# BSAT_-_Battery_Shield.net
KiCad netlist of a schematic drawn in EAGLE
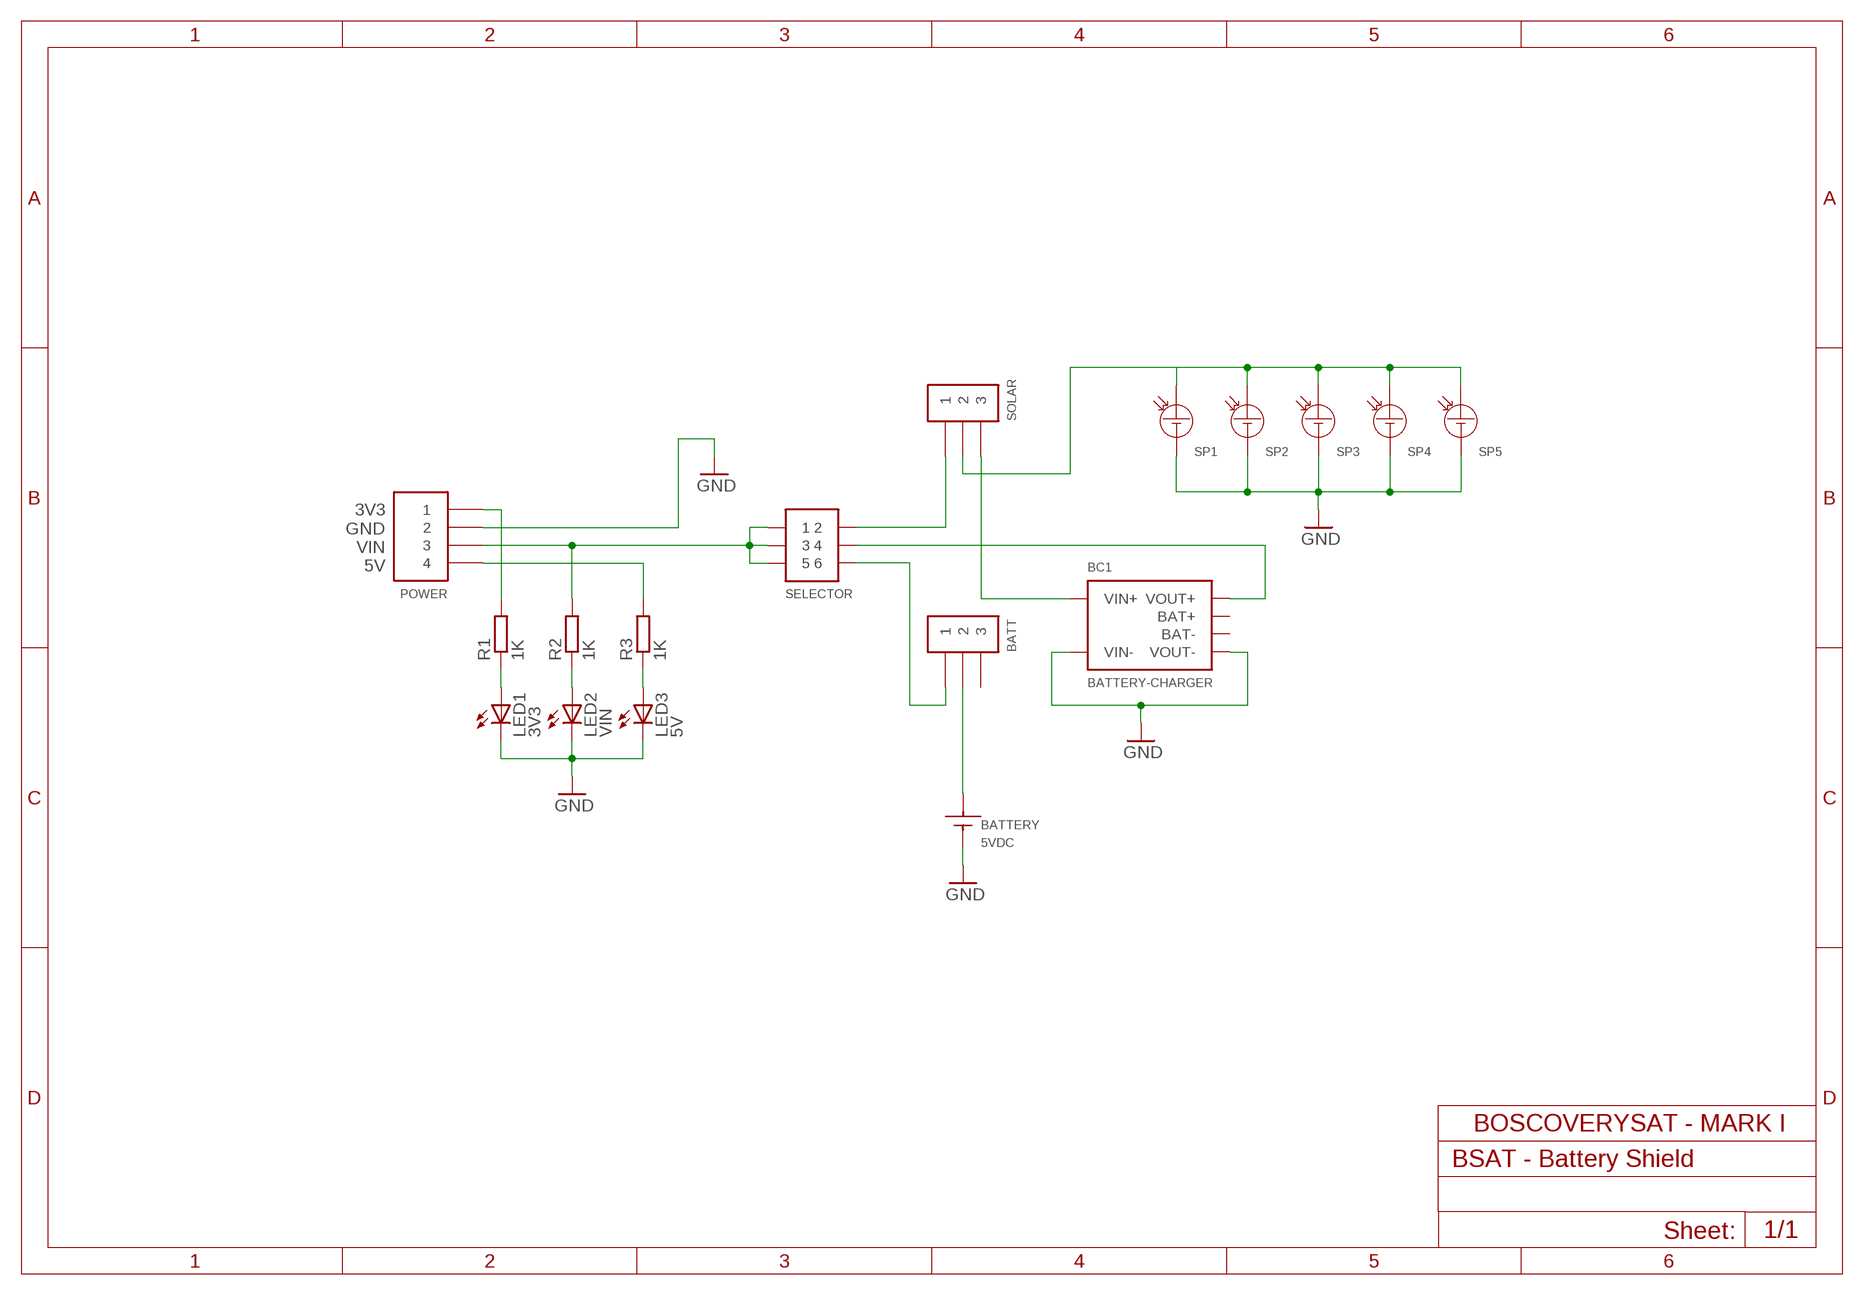
[diagram p0: schematic, sheet 1]

(export (version "E")
  (design (tool "Eeschema 10.0.6"))
  (components
    (comp (ref "5VDC")
      (value "BATTERY")
      (footprint "eagle-import:SOLAR-PANEL")
      (libsource (lib "eagle-import") (part "BATTERY"))
    )
    (comp (ref "BATT")
      (value "3-PIN-JUMPER")
      (footprint "eagle-import:3-PIN-JUMPER")
      (libsource (lib "eagle-import") (part "3-PIN-JUMPER"))
    )
    (comp (ref "BC1")
      (value "BATTERY-CHARGER")
      (footprint "eagle-import:BATTERY-CHARGER")
      (libsource (lib "eagle-import") (part "BATTERY-CHARGER"))
    )
    (comp (ref "LED1")
      (value "3V3")
      (footprint "eagle-import:LED3MM")
      (libsource (lib "eagle-import") (part "LED3MM"))
    )
    (comp (ref "LED2")
      (value "VIN")
      (footprint "eagle-import:LED3MM")
      (libsource (lib "eagle-import") (part "LED3MM"))
    )
    (comp (ref "LED3")
      (value "5V")
      (footprint "eagle-import:LED3MM")
      (libsource (lib "eagle-import") (part "LED3MM"))
    )
    (comp (ref "POWER")
      (value "4-PIN-DUAL-BUS")
      (footprint "eagle-import:4-PIN-LINEAL-JUMPER")
      (libsource (lib "eagle-import") (part "4-PIN-DUAL-BUS"))
    )
    (comp (ref "R1")
      (value "1K")
      (footprint "eagle-import:0207_12")
      (libsource (lib "eagle-import") (part "R-EU_0207/12"))
    )
    (comp (ref "R2")
      (value "1K")
      (footprint "eagle-import:0207_12")
      (libsource (lib "eagle-import") (part "R-EU_0207/12"))
    )
    (comp (ref "R3")
      (value "1K")
      (footprint "eagle-import:0207_12")
      (libsource (lib "eagle-import") (part "R-EU_0207/12"))
    )
    (comp (ref "SELECTOR")
      (value "3-PIN-PARALEL-JUMPER")
      (footprint "eagle-import:3-PIN-PARALEL-JUMPER")
      (libsource (lib "eagle-import") (part "3-PIN-PARALEL-JUMPER"))
    )
    (comp (ref "SOLAR")
      (value "3-PIN-JUMPER")
      (footprint "eagle-import:3-PIN-JUMPER")
      (libsource (lib "eagle-import") (part "3-PIN-JUMPER"))
    )
    (comp (ref "SP1")
      (value "SOLAR-PANEL2")
      (footprint "eagle-import:SOLAR-PANEL")
      (libsource (lib "eagle-import") (part "SOLAR-PANEL2"))
    )
    (comp (ref "SP2")
      (value "SOLAR-PANEL2")
      (footprint "eagle-import:SOLAR-PANEL")
      (libsource (lib "eagle-import") (part "SOLAR-PANEL2"))
    )
    (comp (ref "SP3")
      (value "SOLAR-PANEL2")
      (footprint "eagle-import:SOLAR-PANEL")
      (libsource (lib "eagle-import") (part "SOLAR-PANEL2"))
    )
    (comp (ref "SP4")
      (value "SOLAR-PANEL2")
      (footprint "eagle-import:SOLAR-PANEL")
      (libsource (lib "eagle-import") (part "SOLAR-PANEL2"))
    )
    (comp (ref "SP5")
      (value "SOLAR-PANEL2")
      (footprint "eagle-import:SOLAR-PANEL")
      (libsource (lib "eagle-import") (part "SOLAR-PANEL2"))
    )
  )
  (nets
    (net (code "1") (name "GND") (class "Default")
      (node (ref "5VDC") (pin "NEG") (pinfunction "NEG_NEG") (pintype "bidirectional"))
      (node (ref "BC1") (pin "VIN-") (pinfunction "VIN-_VIN-") (pintype "bidirectional"))
      (node (ref "BC1") (pin "VOUT-") (pinfunction "VOUT-_VOUT-") (pintype "bidirectional"))
      (node (ref "LED1") (pin "K") (pinfunction "C_K") (pintype "passive"))
      (node (ref "LED2") (pin "K") (pinfunction "C_K") (pintype "passive"))
      (node (ref "LED3") (pin "K") (pinfunction "C_K") (pintype "passive"))
      (node (ref "POWER") (pin "2A") (pinfunction "2_2A") (pintype "bidirectional"))
      (node (ref "POWER") (pin "2B") (pinfunction "2_2B") (pintype "bidirectional"))
      (node (ref "SP1") (pin "NEG") (pinfunction "P$2_NEG") (pintype "bidirectional"))
      (node (ref "SP2") (pin "NEG") (pinfunction "P$2_NEG") (pintype "bidirectional"))
      (node (ref "SP3") (pin "NEG") (pinfunction "P$2_NEG") (pintype "bidirectional"))
      (node (ref "SP4") (pin "NEG") (pinfunction "P$2_NEG") (pintype "bidirectional"))
      (node (ref "SP5") (pin "NEG") (pinfunction "P$2_NEG") (pintype "bidirectional"))
    )
    (net (code "2") (name "Net-(5VDC-PadPOS)") (class "Default")
      (node (ref "5VDC") (pin "POS") (pinfunction "POS_POS") (pintype "bidirectional"))
      (node (ref "BATT") (pin "2") (pinfunction "2_2") (pintype "bidirectional"))
    )
    (net (code "3") (name "Net-(BATT-Pad1)") (class "Default")
      (node (ref "BATT") (pin "1") (pinfunction "1_1") (pintype "bidirectional"))
      (node (ref "SELECTOR") (pin "6") (pinfunction "6_6") (pintype "bidirectional"))
    )
    (net (code "4") (name "Net-(BC1-PadVIN+)") (class "Default")
      (node (ref "BC1") (pin "VIN+") (pinfunction "VIN+_VIN+") (pintype "bidirectional"))
      (node (ref "SOLAR") (pin "3") (pinfunction "3_3") (pintype "bidirectional"))
    )
    (net (code "5") (name "Net-(BC1-PadVOUT+)") (class "Default")
      (node (ref "BC1") (pin "VOUT+") (pinfunction "VOUT+_VOUT+") (pintype "bidirectional"))
      (node (ref "SELECTOR") (pin "4") (pinfunction "4_4") (pintype "bidirectional"))
    )
    (net (code "6") (name "Net-(LED1-PadA)") (class "Default")
      (node (ref "LED1") (pin "A") (pinfunction "A_A") (pintype "passive"))
      (node (ref "R1") (pin "1") (pinfunction "1_1") (pintype "passive"))
    )
    (net (code "7") (name "Net-(LED2-PadA)") (class "Default")
      (node (ref "LED2") (pin "A") (pinfunction "A_A") (pintype "passive"))
      (node (ref "R2") (pin "1") (pinfunction "1_1") (pintype "passive"))
    )
    (net (code "8") (name "Net-(LED3-PadA)") (class "Default")
      (node (ref "LED3") (pin "A") (pinfunction "A_A") (pintype "passive"))
      (node (ref "R3") (pin "1") (pinfunction "1_1") (pintype "passive"))
    )
    (net (code "9") (name "Net-(POWER-1-Pad1A)") (class "Default")
      (node (ref "POWER") (pin "1A") (pinfunction "1_1A") (pintype "bidirectional"))
      (node (ref "POWER") (pin "1B") (pinfunction "1_1B") (pintype "bidirectional"))
      (node (ref "R1") (pin "2") (pinfunction "2_2") (pintype "passive"))
    )
    (net (code "10") (name "Net-(POWER-3-Pad3A)") (class "Default")
      (node (ref "POWER") (pin "3A") (pinfunction "3_3A") (pintype "bidirectional"))
      (node (ref "POWER") (pin "3B") (pinfunction "3_3B") (pintype "bidirectional"))
      (node (ref "R2") (pin "2") (pinfunction "2_2") (pintype "passive"))
      (node (ref "SELECTOR") (pin "1") (pinfunction "1_1") (pintype "bidirectional"))
      (node (ref "SELECTOR") (pin "3") (pinfunction "3_3") (pintype "bidirectional"))
      (node (ref "SELECTOR") (pin "5") (pinfunction "5_5") (pintype "bidirectional"))
    )
    (net (code "11") (name "Net-(POWER-4-Pad4A)") (class "Default")
      (node (ref "POWER") (pin "4A") (pinfunction "4_4A") (pintype "bidirectional"))
      (node (ref "POWER") (pin "4B") (pinfunction "4_4B") (pintype "bidirectional"))
      (node (ref "R3") (pin "2") (pinfunction "2_2") (pintype "passive"))
    )
    (net (code "12") (name "Net-(SELECTOR-Pad2)") (class "Default")
      (node (ref "SELECTOR") (pin "2") (pinfunction "2_2") (pintype "bidirectional"))
      (node (ref "SOLAR") (pin "1") (pinfunction "1_1") (pintype "bidirectional"))
    )
    (net (code "13") (name "Net-(SP1-P$1)") (class "Default")
      (node (ref "SOLAR") (pin "2") (pinfunction "2_2") (pintype "bidirectional"))
      (node (ref "SP1") (pin "POS") (pinfunction "P$1_POS") (pintype "bidirectional"))
      (node (ref "SP2") (pin "POS") (pinfunction "P$1_POS") (pintype "bidirectional"))
      (node (ref "SP3") (pin "POS") (pinfunction "P$1_POS") (pintype "bidirectional"))
      (node (ref "SP4") (pin "POS") (pinfunction "P$1_POS") (pintype "bidirectional"))
      (node (ref "SP5") (pin "POS") (pinfunction "P$1_POS") (pintype "bidirectional"))
    )
    (net (code "14") (name "unconnected-(BATT-Pad3)") (class "Default")
      (node (ref "BATT") (pin "3") (pinfunction "3_3") (pintype "bidirectional"))
    )
    (net (code "15") (name "unconnected-(BC1-PadBAT+)") (class "Default")
      (node (ref "BC1") (pin "BAT+") (pinfunction "BAT+_BAT+") (pintype "bidirectional"))
    )
    (net (code "16") (name "unconnected-(BC1-PadBAT-)") (class "Default")
      (node (ref "BC1") (pin "BAT-") (pinfunction "BAT-_BAT-") (pintype "bidirectional"))
    )
  )
)
